# Sinaliza_o_Comunica_o.net
KiCad netlist of a schematic drawn in Altium Designer
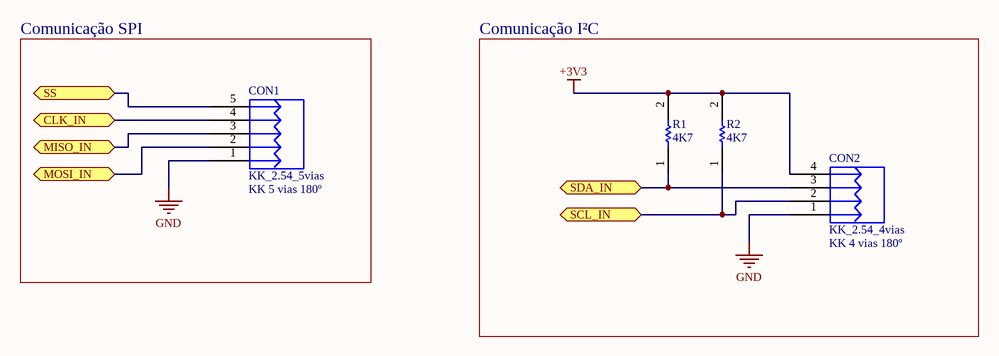
[diagram p0: Sinalização_Comunicação.SchDoc]

(export (version "E")
  (design (tool "Eeschema 10.0.6"))
  (components
    (comp (ref "CON1")
      (value "KK_2.54_5vias")
      (footprint "KK_5vias_180°")
      (description "Conector KK 2.54mm 5 vias")
      (fields (field (name "VALOR") "KK 5 vias 180º"))
      (libsource (lib "Sinalização_Official") (part "KK_2.54_5vias"))
    )
    (comp (ref "CON2")
      (value "KK_2.54_4vias")
      (footprint "KK_4vias_180°")
      (description "Conector KK 2.54mm 4 vias")
      (fields (field (name "VALOR") "KK 4 vias 180º"))
      (libsource (lib "Sinalização_Official") (part "KK_2.54_4vias"))
    )
    (comp (ref "R1")
      (value "4K7")
      (footprint "SamacSys:RESC3216X60N")
      (description "Resistor")
      (fields
        (field (name "MANUFACTURER_PART_NUMBER") "CRCW12064K70FKEA")
        (field (name "MOUSER PART NUMBER") "71-CRCW1206-4.7K-E3")
      )
      (libsource (lib "Sinalização_Official") (part "Resistor 1206"))
    )
    (comp (ref "R2")
      (value "4K7")
      (footprint "SamacSys:RESC3216X60N")
      (description "Resistor")
      (fields
        (field (name "MANUFACTURER_PART_NUMBER") "CRCW12064K70FKEA")
        (field (name "MOUSER PART NUMBER") "71-CRCW1206-4.7K-E3")
      )
      (libsource (lib "Sinalização_Official") (part "Resistor 1206"))
    )
  )
  (nets
    (net (code "1") (name "+3V3") (class "Default")
      (node (ref "CON2") (pin "4") (pintype "passive"))
      (node (ref "R1") (pin "2") (pinfunction "2_2") (pintype "passive"))
      (node (ref "R2") (pin "2") (pinfunction "2_2") (pintype "passive"))
    )
    (net (code "2") (name "/CLK_IN") (class "Default") (node (ref "CON1") (pin "4") (pintype "passive")))
    (net (code "3") (name "/MISO_IN") (class "Default") (node (ref "CON1") (pin "3") (pintype "passive")))
    (net (code "4") (name "/MOSI_IN") (class "Default") (node (ref "CON1") (pin "2") (pintype "passive")))
    (net (code "5") (name "/SCL_IN") (class "Default")
      (node (ref "CON2") (pin "2") (pintype "passive"))
      (node (ref "R2") (pin "1") (pinfunction "1_1") (pintype "passive"))
    )
    (net (code "6") (name "/SDA_IN") (class "Default")
      (node (ref "CON2") (pin "3") (pintype "passive"))
      (node (ref "R1") (pin "1") (pinfunction "1_1") (pintype "passive"))
    )
    (net (code "7") (name "/SS") (class "Default") (node (ref "CON1") (pin "5") (pintype "passive")))
    (net (code "8") (name "GND") (class "Default")
      (node (ref "CON1") (pin "1") (pintype "passive"))
      (node (ref "CON2") (pin "1") (pintype "passive"))
    )
  )
)
